# Sheet1.net
KiCad netlist of a schematic drawn in Altium Designer
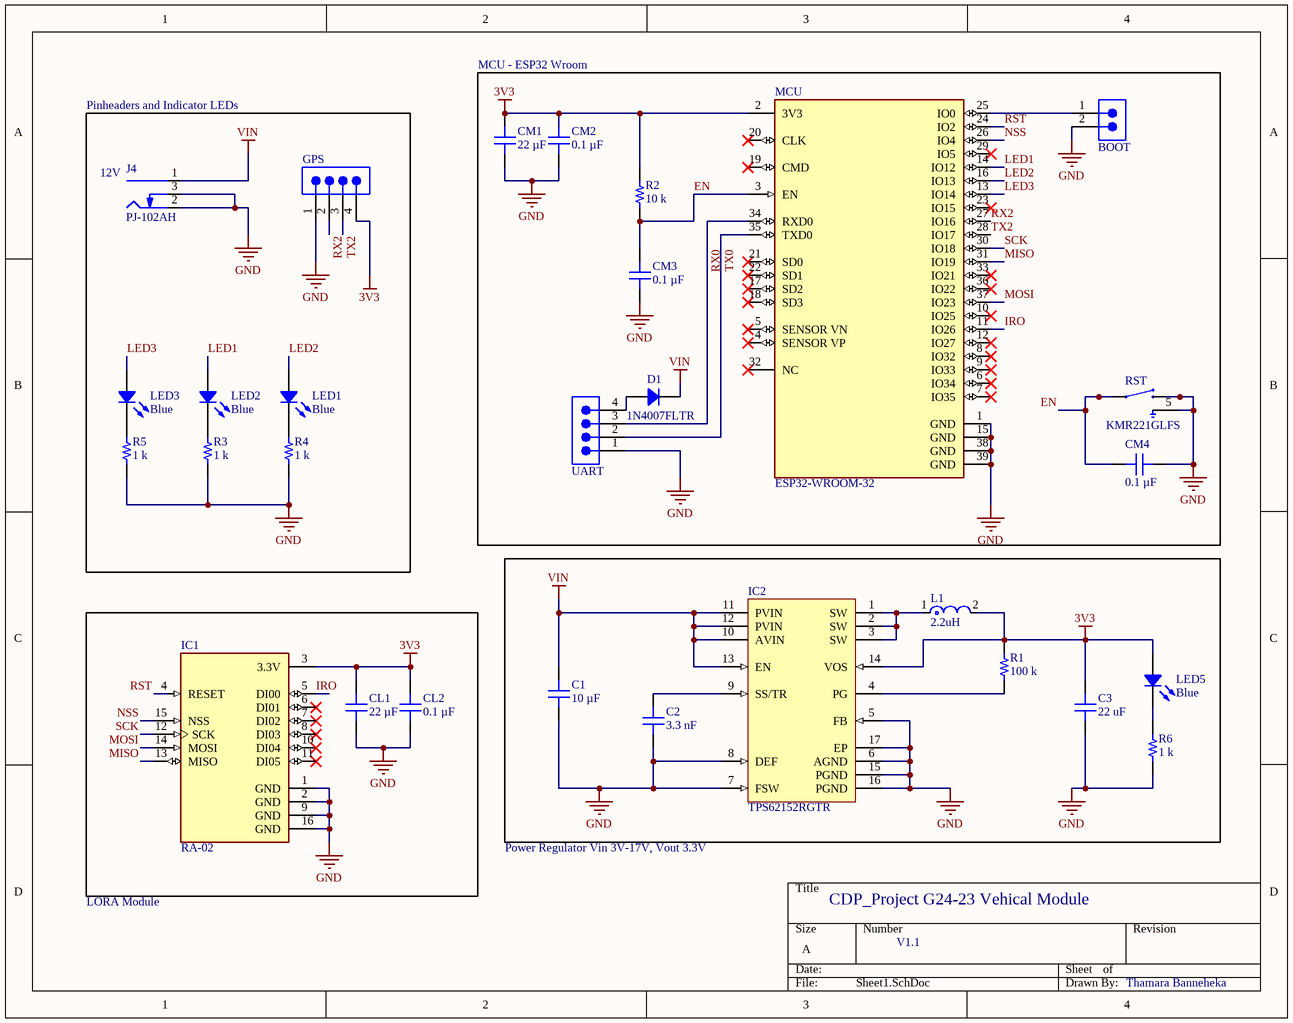
[diagram p0: Sheet1.SchDoc]

(export (version "E")
  (design (tool "Eeschema 10.0.6"))
  (components
    (comp (ref "BOOT")
      (value "CMP-011-000133-1")
      (footprint "61300211121")
      (description "WR-PHD Pin Header, THT, Vertical, pitch 2.54mm, 1 Row, 2P")
      (fields
        (field (name "MANUFACTURER PART NUMBER") "61300211121")
        (field (name "MANUFACTURER") "Wurth Elektronik")
      )
      (libsource (lib "Thamara Banneheka") (part "62000211121"))
    )
    (comp (ref "C1")
      (value "10 µF")
      (footprint "CAP 0805_2012")
      (description "CAP CER 10UF 16V X6S 0805")
      (fields
        (field (name "PART NUMBER") "C2012X6S1C106K125AC")
        (field (name "CAPACITANCE") "10 µF")
        (field (name "MANUFACTURER") "TDK Corporation")
      )
      (libsource (lib "Celestial Altium Library - altium_library") (part "Capacitor"))
    )
    (comp (ref "C2")
      (value "3300 pF")
      (footprint "CAP 0805_2012")
      (description "CAP CER 0805 3.3NF 50V C0G 1%")
      (fields
        (field (name "PART NUMBER") "C0805C332F5GECAUTO")
        (field (name "CAPACITANCE") "3.3 nF")
        (field (name "MANUFACTURER") "KEMET")
      )
      (libsource (lib "Celestial Altium Library - altium_library") (part "Capacitor"))
    )
    (comp (ref "C3")
      (value "0.022 µF")
      (footprint "CAP 0805_2012")
      (description "CAP CER 0805 22NF 50V X7R 10%")
      (fields
        (field (name "PART NUMBER") "C0805C223K5RECAUTO")
        (field (name "CAPACITANCE") "22 uF")
        (field (name "MANUFACTURER") "KEMET")
      )
      (libsource (lib "Celestial Altium Library - altium_library") (part "Capacitor"))
    )
    (comp (ref "CL1")
      (value "22 µF")
      (footprint "CAP 0805_2012")
      (description "CAP CER 22UF 16V X5R 0805")
      (fields
        (field (name "PART NUMBER") "CL21A226KOQNNNG")
        (field (name "CAPACITANCE") "22 µF")
        (field (name "MANUFACTURER") "Samsung Electro-Mechanics")
      )
      (libsource (lib "Celestial Altium Library - altium_library") (part "Capacitor"))
    )
    (comp (ref "CL2")
      (value "0.1 µF")
      (footprint "CAP 0805_2012")
      (description "CAP CER 0.1UF 50V X7R 0805")
      (fields
        (field (name "PART NUMBER") "CC0805MRX7R9BB104")
        (field (name "CAPACITANCE") "0.1 µF")
        (field (name "MANUFACTURER") "Yageo")
      )
      (libsource (lib "Celestial Altium Library - altium_library") (part "Capacitor"))
    )
    (comp (ref "CM1")
      (value "22 µF")
      (footprint "CAP 0805_2012")
      (description "CAP CER 22UF 16V X5R 0805")
      (fields
        (field (name "PART NUMBER") "CL21A226KOQNNNG")
        (field (name "CAPACITANCE") "22 µF")
        (field (name "MANUFACTURER") "Samsung Electro-Mechanics")
      )
      (libsource (lib "Celestial Altium Library - altium_library") (part "Capacitor"))
    )
    (comp (ref "CM2")
      (value "0.1 µF")
      (footprint "CAP 0805_2012")
      (description "CAP CER 0.1UF 50V X7R 0805")
      (fields
        (field (name "PART NUMBER") "CC0805MRX7R9BB104")
        (field (name "CAPACITANCE") "0.1 µF")
        (field (name "MANUFACTURER") "Yageo")
      )
      (libsource (lib "Celestial Altium Library - altium_library") (part "Capacitor"))
    )
    (comp (ref "CM3")
      (value "0.1 µF")
      (footprint "CAP 0805_2012")
      (description "CAP CER 0.1UF 50V X7R 0805")
      (fields
        (field (name "PART NUMBER") "CC0805MRX7R9BB104")
        (field (name "CAPACITANCE") "0.1 µF")
        (field (name "MANUFACTURER") "Yageo")
      )
      (libsource (lib "Celestial Altium Library - altium_library") (part "Capacitor"))
    )
    (comp (ref "CM4")
      (value "0.1 µF")
      (footprint "CAP 0805_2012")
      (description "CAP CER 0.1UF 50V X7R 0805")
      (fields
        (field (name "PART NUMBER") "CC0805MRX7R9BB104")
        (field (name "CAPACITANCE") "0.1 µF")
        (field (name "MANUFACTURER") "Yageo")
      )
      (libsource (lib "Celestial Altium Library - altium_library") (part "Capacitor"))
    )
    (comp (ref "D1")
      (value "1N4007FLTR")
      (footprint "SOD123F")
      (description "STANDARD RECTIFIER 1000V SOD-123")
      (fields (field (name "MANUFACTURER") "SMC Diode Solutions"))
      (libsource (lib "Celestial Altium Library - altium_library") (part "Diode"))
    )
    (comp (ref "GPS")
      (value "CMP-011-000141-1")
      (footprint "61300411121")
      (description "WR-PHD Pin Header, THT, Vertical, pitch 2.54mm, 1 Row, 4P")
      (fields
        (field (name "MANUFACTURER PART NUMBER") "61300411121")
        (field (name "MANUFACTURER") "Wurth Elektronik")
      )
      (libsource (lib "Thamara Banneheka") (part "62000411121"))
    )
    (comp (ref "IC1")
      (value "RA-02")
      (footprint "RA-02")
      (fields (field (name "MF") "Ai-Thinker"))
      (libsource (lib "Thamara Banneheka") (part "RA-02"))
    )
    (comp (ref "IC2")
      (value "TPS62152RGTR")
      (footprint "RGT0016C_V")
      (fields (field (name "MANUFACTURER") "Texas Instruments"))
      (libsource (lib "Altium Content Vault") (part "TI-TPS62152RGT16-1700X1700TP"))
    )
    (comp (ref "J4")
      (value "PJ-102AH")
      (footprint "CUI PJ-102AH")
      (description "CONN PWR JACK 2X5.5MM SOLDER")
      (fields (field (name "MANUFACTURER") "CUI Devices"))
      (libsource (lib "Celestial Altium Library - altium_library") (part "Barrel Connector"))
    )
    (comp (ref "L1")
      (value "2.2uH")
      (footprint "FP-XFL4020-MFG")
      (description "INDUCTOR, 2.2UH, 8A, 20%, 38MHZ, REEL")
      (fields (field (name "TOLERANCE") "20%"))
      (libsource (lib "Altium Content Vault") (part "4cc4b267dca4c8e51f7102f422741d8"))
    )
    (comp (ref "LED1")
      (value "Blue")
      (footprint "LED 0603_1608 BLUE")
      (description "LED BLUE CLEAR 0603 SMD")
      (fields (field (name "PART NUMBER") "SM0603UBWC") (field (name "MANUFACTURER") "Bivar Inc."))
      (libsource (lib "Celestial Altium Library - altium_library") (part "LED"))
    )
    (comp (ref "LED2")
      (value "Blue")
      (footprint "LED 0603_1608 BLUE")
      (description "LED BLUE CLEAR 0603 SMD")
      (fields (field (name "PART NUMBER") "SM0603UBWC") (field (name "MANUFACTURER") "Bivar Inc."))
      (libsource (lib "Celestial Altium Library - altium_library") (part "LED"))
    )
    (comp (ref "LED3")
      (value "Blue")
      (footprint "LED 0603_1608 BLUE")
      (description "LED BLUE CLEAR 0603 SMD")
      (fields (field (name "PART NUMBER") "SM0603UBWC") (field (name "MANUFACTURER") "Bivar Inc."))
      (libsource (lib "Celestial Altium Library - altium_library") (part "LED"))
    )
    (comp (ref "LED5")
      (value "Blue")
      (footprint "LED 0603_1608 BLUE")
      (description "LED BLUE CLEAR CHIP 0603 SMD")
      (fields
        (field (name "PART NUMBER") "LSM0603463V")
        (field (name "MANUFACTURER") "Visual Communications Company - VCC")
      )
      (libsource (lib "Celestial Altium Library - altium_library") (part "LED"))
    )
    (comp (ref "MCU")
      (value "ESP32-WROOM-32")
      (footprint "FP-ESP32-WROOM-32-MFG")
      (description "RX TXRX MOD WIFI SURFACE MOUNT")
      (libsource (lib "Altium Content Vault") (part "ee866abf0b6c51247b7f5cdebf2f250"))
    )
    (comp (ref "R1")
      (value "100 k")
      (footprint "RES 0805_2012")
      (description "RES SMD 100K OHM 1% 1/2W 0805")
      (fields (field (name "PART NUMBER") "RCS0805100KFKEA") (field (name "MANUFACTURER") "Vishay Dale"))
      (libsource (lib "Celestial Altium Library - altium_library") (part "Resistor"))
    )
    (comp (ref "R2")
      (value "10 k")
      (footprint "RES 0805_2012")
      (description "RES SMD 100K OHM 1% 1/2W 0805")
      (fields (field (name "PART NUMBER") "RCS0805100KFKEA") (field (name "MANUFACTURER") "Vishay Dale"))
      (libsource (lib "Celestial Altium Library - altium_library") (part "Resistor"))
    )
    (comp (ref "R3")
      (value "1 k")
      (footprint "RES 0805_2012")
      (description "RES SMD 100K OHM 1% 1/2W 0805")
      (fields (field (name "PART NUMBER") "RCS0805100KFKEA") (field (name "MANUFACTURER") "Vishay Dale"))
      (libsource (lib "Celestial Altium Library - altium_library") (part "Resistor"))
    )
    (comp (ref "R4")
      (value "1 k")
      (footprint "RES 0805_2012")
      (description "RES SMD 100K OHM 1% 1/2W 0805")
      (fields (field (name "PART NUMBER") "RCS0805100KFKEA") (field (name "MANUFACTURER") "Vishay Dale"))
      (libsource (lib "Celestial Altium Library - altium_library") (part "Resistor"))
    )
    (comp (ref "R5")
      (value "1 k")
      (footprint "RES 0805_2012")
      (description "RES SMD 100K OHM 1% 1/2W 0805")
      (fields (field (name "PART NUMBER") "RCS0805100KFKEA") (field (name "MANUFACTURER") "Vishay Dale"))
      (libsource (lib "Celestial Altium Library - altium_library") (part "Resistor"))
    )
    (comp (ref "R6")
      (value "1 k")
      (footprint "RES 0805_2012")
      (description "RES SMD 100K OHM 1% 1/2W 0805")
      (fields (field (name "PART NUMBER") "RCS0805100KFKEA") (field (name "MANUFACTURER") "Vishay Dale"))
      (libsource (lib "Celestial Altium Library - altium_library") (part "Resistor"))
    )
    (comp (ref "RST")
      (value "KMR221GLFS")
      (footprint "SW_KMR221GLFS")
      (description "Switch Tactile N.O. SPST Button Gull Wing 0.05A 32VDC 1VA 200000Cycles 2N SMD Automotive T/R")
      (libsource (lib "Thamara Banneheka") (part "KMR221GLFS"))
    )
    (comp (ref "UART")
      (value "CMP-011-000141-1")
      (footprint "61300411121")
      (description "WR-PHD Pin Header, THT, Vertical, pitch 2.54mm, 1 Row, 4P")
      (fields
        (field (name "MANUFACTURER PART NUMBER") "61300411121")
        (field (name "MANUFACTURER") "Wurth Elektronik")
      )
      (libsource (lib "Thamara Banneheka") (part "62000411121"))
    )
  )
  (nets
    (net (code "1") (name "/EN") (class "Default")
      (node (ref "CM3") (pin "2") (pinfunction "2_2") (pintype "passive"))
      (node (ref "CM4") (pin "2") (pinfunction "2_2") (pintype "passive"))
      (node (ref "MCU") (pin "3") (pinfunction "EN_3") (pintype "input"))
      (node (ref "R2") (pin "1") (pinfunction "1_1") (pintype "passive"))
      (node (ref "RST") (pin "1") (pinfunction "1_1") (pintype "passive"))
      (node (ref "RST") (pin "4") (pinfunction "1_4") (pintype "passive"))
    )
    (net (code "2") (name "/IRO") (class "Default")
      (node (ref "IC1") (pin "5") (pinfunction "DI00_5") (pintype "bidirectional"))
      (node (ref "MCU") (pin "11") (pinfunction "IO26_11") (pintype "bidirectional"))
    )
    (net (code "3") (name "/LED1") (class "Default")
      (node (ref "LED2") (pin "1") (pinfunction "1_1") (pintype "passive"))
      (node (ref "MCU") (pin "14") (pinfunction "IO12_14") (pintype "bidirectional"))
    )
    (net (code "4") (name "/LED2") (class "Default")
      (node (ref "LED1") (pin "1") (pinfunction "1_1") (pintype "passive"))
      (node (ref "MCU") (pin "16") (pinfunction "IO13_16") (pintype "bidirectional"))
    )
    (net (code "5") (name "/LED3") (class "Default")
      (node (ref "LED3") (pin "1") (pinfunction "1_1") (pintype "passive"))
      (node (ref "MCU") (pin "13") (pinfunction "IO14_13") (pintype "bidirectional"))
    )
    (net (code "6") (name "/MISO") (class "Default")
      (node (ref "IC1") (pin "13") (pinfunction "MISO_13") (pintype "bidirectional"))
      (node (ref "MCU") (pin "31") (pinfunction "IO19_31") (pintype "bidirectional"))
    )
    (net (code "7") (name "/MOSI") (class "Default")
      (node (ref "IC1") (pin "14") (pinfunction "MOSI_14") (pintype "input"))
      (node (ref "MCU") (pin "37") (pinfunction "IO23_37") (pintype "bidirectional"))
    )
    (net (code "8") (name "/NSS") (class "Default")
      (node (ref "IC1") (pin "15") (pinfunction "NSS_15") (pintype "input"))
      (node (ref "MCU") (pin "26") (pinfunction "IO4_26") (pintype "bidirectional"))
    )
    (net (code "9") (name "/RST") (class "Default")
      (node (ref "IC1") (pin "4") (pinfunction "RESET_4") (pintype "input"))
      (node (ref "MCU") (pin "24") (pinfunction "IO2_24") (pintype "bidirectional"))
    )
    (net (code "10") (name "/RX0") (class "Default")
      (node (ref "MCU") (pin "34") (pinfunction "RXD0_34") (pintype "bidirectional"))
      (node (ref "UART") (pin "3") (pinfunction "3_3") (pintype "passive"))
    )
    (net (code "11") (name "/RX2") (class "Default")
      (node (ref "GPS") (pin "2") (pinfunction "2_2") (pintype "passive"))
      (node (ref "MCU") (pin "27") (pinfunction "IO16_27") (pintype "bidirectional"))
    )
    (net (code "12") (name "/SCK") (class "Default")
      (node (ref "IC1") (pin "12") (pinfunction "SCK_12") (pintype "input"))
      (node (ref "MCU") (pin "30") (pinfunction "IO18_30") (pintype "bidirectional"))
    )
    (net (code "13") (name "/TX0") (class "Default")
      (node (ref "MCU") (pin "35") (pinfunction "TXD0_35") (pintype "bidirectional"))
      (node (ref "UART") (pin "2") (pinfunction "2_2") (pintype "passive"))
    )
    (net (code "14") (name "/TX2") (class "Default")
      (node (ref "GPS") (pin "3") (pinfunction "3_3") (pintype "passive"))
      (node (ref "MCU") (pin "28") (pinfunction "IO17_28") (pintype "bidirectional"))
    )
    (net (code "15") (name "3V3") (class "Default")
      (node (ref "C3") (pin "2") (pinfunction "2_2") (pintype "passive"))
      (node (ref "CL1") (pin "2") (pinfunction "2_2") (pintype "passive"))
      (node (ref "CL2") (pin "2") (pinfunction "2_2") (pintype "passive"))
      (node (ref "CM1") (pin "2") (pinfunction "2_2") (pintype "passive"))
      (node (ref "CM2") (pin "2") (pinfunction "2_2") (pintype "passive"))
      (node (ref "GPS") (pin "4") (pinfunction "4_4") (pintype "passive"))
      (node (ref "IC1") (pin "3") (pinfunction "3.3V_3") (pintype "power_in"))
      (node (ref "IC2") (pin "14") (pinfunction "VOS_14") (pintype "input"))
      (node (ref "L1") (pin "2") (pinfunction "2_2") (pintype "passive"))
      (node (ref "LED5") (pin "1") (pinfunction "1_1") (pintype "passive"))
      (node (ref "MCU") (pin "2") (pinfunction "3V3_2") (pintype "power_in"))
      (node (ref "R1") (pin "2") (pinfunction "2_2") (pintype "passive"))
      (node (ref "R2") (pin "2") (pinfunction "2_2") (pintype "passive"))
    )
    (net (code "16") (name "GND") (class "Default")
      (node (ref "BOOT") (pin "2") (pinfunction "2_2") (pintype "passive"))
      (node (ref "C1") (pin "1") (pinfunction "1_1") (pintype "passive"))
      (node (ref "C2") (pin "1") (pinfunction "1_1") (pintype "passive"))
      (node (ref "C3") (pin "1") (pinfunction "1_1") (pintype "passive"))
      (node (ref "CL1") (pin "1") (pinfunction "1_1") (pintype "passive"))
      (node (ref "CL2") (pin "1") (pinfunction "1_1") (pintype "passive"))
      (node (ref "CM1") (pin "1") (pinfunction "1_1") (pintype "passive"))
      (node (ref "CM2") (pin "1") (pinfunction "1_1") (pintype "passive"))
      (node (ref "CM3") (pin "1") (pinfunction "1_1") (pintype "passive"))
      (node (ref "CM4") (pin "1") (pinfunction "1_1") (pintype "passive"))
      (node (ref "GPS") (pin "1") (pinfunction "1_1") (pintype "passive"))
      (node (ref "IC1") (pin "1") (pinfunction "GND_1") (pintype "power_in"))
      (node (ref "IC1") (pin "16") (pinfunction "GND_16") (pintype "power_in"))
      (node (ref "IC1") (pin "2") (pinfunction "GND_2") (pintype "power_in"))
      (node (ref "IC1") (pin "9") (pinfunction "GND_9") (pintype "power_in"))
      (node (ref "IC2") (pin "15") (pinfunction "PGND_15") (pintype "power_in"))
      (node (ref "IC2") (pin "16") (pinfunction "PGND_16") (pintype "power_in"))
      (node (ref "IC2") (pin "17") (pinfunction "EP_17") (pintype "power_in"))
      (node (ref "IC2") (pin "5") (pinfunction "FB_5") (pintype "input"))
      (node (ref "IC2") (pin "6") (pinfunction "AGND_6") (pintype "power_in"))
      (node (ref "IC2") (pin "7") (pinfunction "FSW_7") (pintype "input"))
      (node (ref "IC2") (pin "8") (pinfunction "DEF_8") (pintype "input"))
      (node (ref "J4") (pin "2") (pinfunction "Outer_2") (pintype "passive"))
      (node (ref "J4") (pin "3") (pinfunction "SW_3") (pintype "passive"))
      (node (ref "MCU") (pin "1") (pinfunction "GND_1") (pintype "power_in"))
      (node (ref "MCU") (pin "15") (pinfunction "GND_15") (pintype "power_in"))
      (node (ref "MCU") (pin "38") (pinfunction "GND_38") (pintype "power_in"))
      (node (ref "MCU") (pin "39") (pinfunction "GND_39") (pintype "power_in"))
      (node (ref "R3") (pin "1") (pinfunction "1_1") (pintype "passive"))
      (node (ref "R4") (pin "1") (pinfunction "1_1") (pintype "passive"))
      (node (ref "R5") (pin "1") (pinfunction "1_1") (pintype "passive"))
      (node (ref "R6") (pin "1") (pinfunction "1_1") (pintype "passive"))
      (node (ref "RST") (pin "2") (pinfunction "3_2") (pintype "passive"))
      (node (ref "RST") (pin "3") (pinfunction "3_3") (pintype "passive"))
      (node (ref "RST") (pin "5") (pinfunction "5_5") (pintype "passive"))
      (node (ref "UART") (pin "1") (pinfunction "1_1") (pintype "passive"))
    )
    (net (code "17") (name "Net-(D1-Pad1)") (class "Default")
      (node (ref "D1") (pin "1") (pinfunction "1_1") (pintype "passive"))
      (node (ref "UART") (pin "4") (pinfunction "4_4") (pintype "passive"))
    )
    (net (code "18") (name "Net-(IC2-PG)") (class "Default")
      (node (ref "IC2") (pin "4") (pinfunction "PG_4") (pintype "tri_state"))
      (node (ref "R1") (pin "1") (pinfunction "1_1") (pintype "passive"))
    )
    (net (code "19") (name "Net-(IC2-SS{slash}TR)") (class "Default")
      (node (ref "C2") (pin "2") (pinfunction "2_2") (pintype "passive"))
      (node (ref "IC2") (pin "9") (pinfunction "SS/TR_9") (pintype "input"))
    )
    (net (code "20") (name "Net-(IC2-SW-Pad1)") (class "Default")
      (node (ref "IC2") (pin "1") (pinfunction "SW_1") (pintype "power_in"))
      (node (ref "IC2") (pin "2") (pinfunction "SW_2") (pintype "power_in"))
      (node (ref "IC2") (pin "3") (pinfunction "SW_3") (pintype "power_in"))
      (node (ref "L1") (pin "1") (pinfunction "1_1") (pintype "passive"))
    )
    (net (code "21") (name "Net-(LED1-Pad2)") (class "Default")
      (node (ref "LED1") (pin "2") (pinfunction "2_2") (pintype "passive"))
      (node (ref "R4") (pin "2") (pinfunction "2_2") (pintype "passive"))
    )
    (net (code "22") (name "Net-(LED2-Pad2)") (class "Default")
      (node (ref "LED2") (pin "2") (pinfunction "2_2") (pintype "passive"))
      (node (ref "R3") (pin "2") (pinfunction "2_2") (pintype "passive"))
    )
    (net (code "23") (name "Net-(LED3-Pad2)") (class "Default")
      (node (ref "LED3") (pin "2") (pinfunction "2_2") (pintype "passive"))
      (node (ref "R5") (pin "2") (pinfunction "2_2") (pintype "passive"))
    )
    (net (code "24") (name "Net-(LED5-Pad2)") (class "Default")
      (node (ref "LED5") (pin "2") (pinfunction "2_2") (pintype "passive"))
      (node (ref "R6") (pin "2") (pinfunction "2_2") (pintype "passive"))
    )
    (net (code "25") (name "Net-(MCU-IO0)") (class "Default")
      (node (ref "BOOT") (pin "1") (pinfunction "1_1") (pintype "passive"))
      (node (ref "MCU") (pin "25") (pinfunction "IO0_25") (pintype "bidirectional"))
    )
    (net (code "26") (name "VIN") (class "Default")
      (node (ref "C1") (pin "2") (pinfunction "2_2") (pintype "passive"))
      (node (ref "D1") (pin "2") (pinfunction "2_2") (pintype "passive"))
      (node (ref "IC2") (pin "10") (pinfunction "AVIN_10") (pintype "power_in"))
      (node (ref "IC2") (pin "11") (pinfunction "PVIN_11") (pintype "power_in"))
      (node (ref "IC2") (pin "12") (pinfunction "PVIN_12") (pintype "power_in"))
      (node (ref "IC2") (pin "13") (pinfunction "EN_13") (pintype "input"))
      (node (ref "J4") (pin "1") (pinfunction "Centre_1") (pintype "passive"))
    )
    (net (code "27") (name "unconnected-(IC1-DI01-Pad6)") (class "Default")
      (node (ref "IC1") (pin "6") (pinfunction "DI01_6") (pintype "bidirectional+no_connect"))
    )
    (net (code "28") (name "unconnected-(IC1-DI02-Pad7)") (class "Default")
      (node (ref "IC1") (pin "7") (pinfunction "DI02_7") (pintype "bidirectional+no_connect"))
    )
    (net (code "29") (name "unconnected-(IC1-DI03-Pad8)") (class "Default")
      (node (ref "IC1") (pin "8") (pinfunction "DI03_8") (pintype "bidirectional+no_connect"))
    )
    (net (code "30") (name "unconnected-(IC1-DI04-Pad10)") (class "Default")
      (node (ref "IC1") (pin "10") (pinfunction "DI04_10") (pintype "bidirectional+no_connect"))
    )
    (net (code "31") (name "unconnected-(IC1-DI05-Pad11)") (class "Default")
      (node (ref "IC1") (pin "11") (pinfunction "DI05_11") (pintype "bidirectional+no_connect"))
    )
    (net (code "32") (name "unconnected-(MCU-CLK-Pad20)") (class "Default")
      (node (ref "MCU") (pin "20") (pinfunction "CLK_20") (pintype "bidirectional+no_connect"))
    )
    (net (code "33") (name "unconnected-(MCU-CMD-Pad19)") (class "Default")
      (node (ref "MCU") (pin "19") (pinfunction "CMD_19") (pintype "bidirectional+no_connect"))
    )
    (net (code "34") (name "unconnected-(MCU-IO5-Pad29)") (class "Default")
      (node (ref "MCU") (pin "29") (pinfunction "IO5_29") (pintype "bidirectional+no_connect"))
    )
    (net (code "35") (name "unconnected-(MCU-IO15-Pad23)") (class "Default")
      (node (ref "MCU") (pin "23") (pinfunction "IO15_23") (pintype "bidirectional+no_connect"))
    )
    (net (code "36") (name "unconnected-(MCU-IO21-Pad33)") (class "Default")
      (node (ref "MCU") (pin "33") (pinfunction "IO21_33") (pintype "bidirectional+no_connect"))
    )
    (net (code "37") (name "unconnected-(MCU-IO22-Pad36)") (class "Default")
      (node (ref "MCU") (pin "36") (pinfunction "IO22_36") (pintype "bidirectional+no_connect"))
    )
    (net (code "38") (name "unconnected-(MCU-IO25-Pad10)") (class "Default")
      (node (ref "MCU") (pin "10") (pinfunction "IO25_10") (pintype "bidirectional+no_connect"))
    )
    (net (code "39") (name "unconnected-(MCU-IO27-Pad12)") (class "Default")
      (node (ref "MCU") (pin "12") (pinfunction "IO27_12") (pintype "bidirectional+no_connect"))
    )
    (net (code "40") (name "unconnected-(MCU-IO32-Pad8)") (class "Default")
      (node (ref "MCU") (pin "8") (pinfunction "IO32_8") (pintype "bidirectional+no_connect"))
    )
    (net (code "41") (name "unconnected-(MCU-IO33-Pad9)") (class "Default")
      (node (ref "MCU") (pin "9") (pinfunction "IO33_9") (pintype "bidirectional+no_connect"))
    )
    (net (code "42") (name "unconnected-(MCU-IO34-Pad6)") (class "Default")
      (node (ref "MCU") (pin "6") (pinfunction "IO34_6") (pintype "bidirectional+no_connect"))
    )
    (net (code "43") (name "unconnected-(MCU-IO35-Pad7)") (class "Default")
      (node (ref "MCU") (pin "7") (pinfunction "IO35_7") (pintype "bidirectional+no_connect"))
    )
    (net (code "44") (name "unconnected-(MCU-NC-Pad32)") (class "Default")
      (node (ref "MCU") (pin "32") (pinfunction "NC_32") (pintype "passive+no_connect"))
    )
    (net (code "45") (name "unconnected-(MCU-SD0-Pad21)") (class "Default")
      (node (ref "MCU") (pin "21") (pinfunction "SD0_21") (pintype "bidirectional+no_connect"))
    )
    (net (code "46") (name "unconnected-(MCU-SD1-Pad22)") (class "Default")
      (node (ref "MCU") (pin "22") (pinfunction "SD1_22") (pintype "bidirectional+no_connect"))
    )
    (net (code "47") (name "unconnected-(MCU-SD2-Pad17)") (class "Default")
      (node (ref "MCU") (pin "17") (pinfunction "SD2_17") (pintype "bidirectional+no_connect"))
    )
    (net (code "48") (name "unconnected-(MCU-SD3-Pad18)") (class "Default")
      (node (ref "MCU") (pin "18") (pinfunction "SD3_18") (pintype "bidirectional+no_connect"))
    )
    (net (code "49") (name "unconnected-(MCU-SENSOR_VN-Pad5)") (class "Default")
      (node (ref "MCU") (pin "5") (pinfunction "SENSOR_VN_5") (pintype "bidirectional+no_connect"))
    )
    (net (code "50") (name "unconnected-(MCU-SENSOR_VP-Pad4)") (class "Default")
      (node (ref "MCU") (pin "4") (pinfunction "SENSOR_VP_4") (pintype "bidirectional+no_connect"))
    )
  )
)
